# LMP9100_breakout.net
KiCad netlist of a schematic drawn in EAGLE
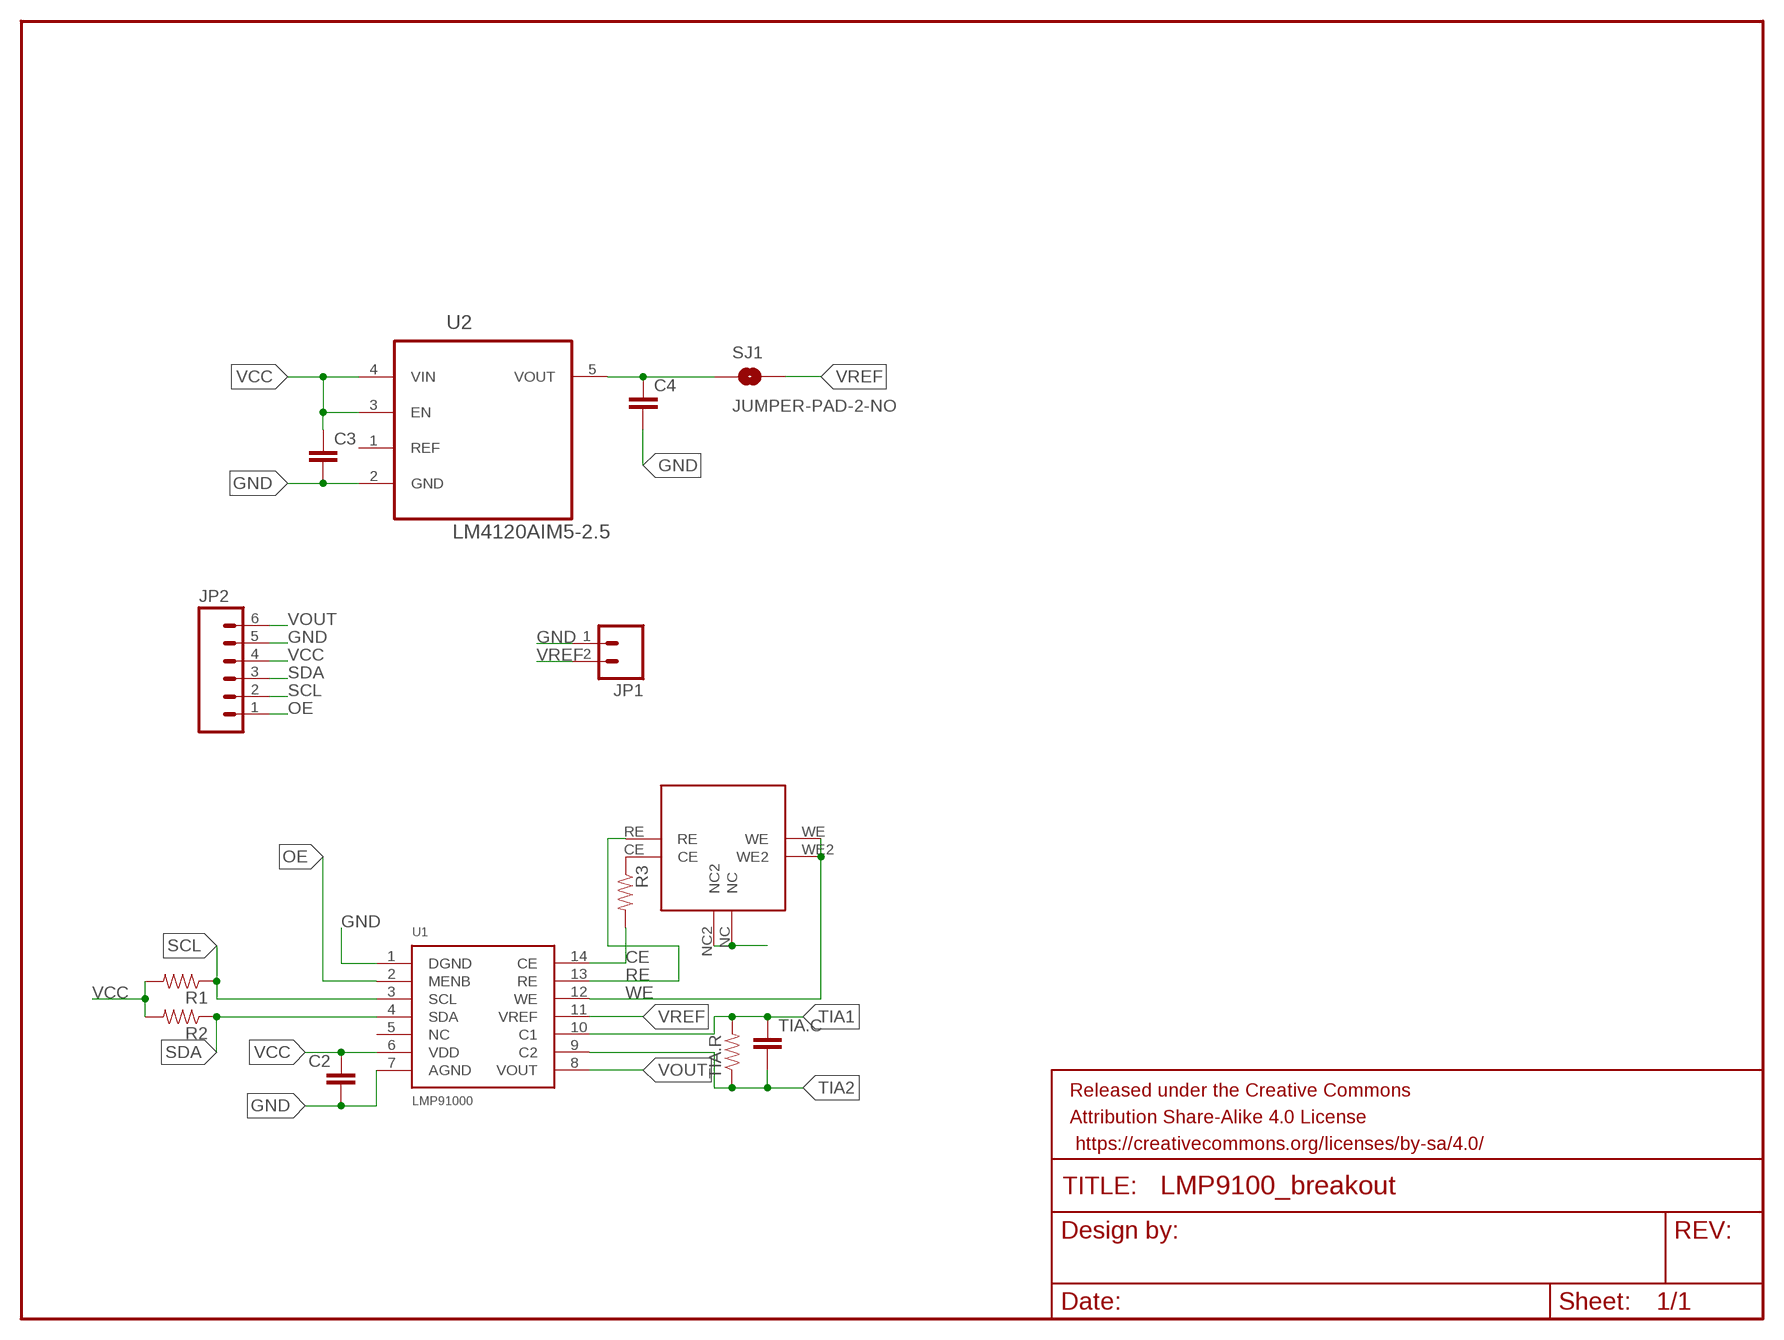
[diagram p0: schematic, sheet 1]

(export (version "E")
  (design (tool "Eeschema 10.0.6"))
  (components
    (comp (ref "C2")
      (value "CAP0603-CAP")
      (footprint "eagle-import:0603-CAP")
      (libsource (lib "eagle-import") (part "CAP0603-CAP"))
    )
    (comp (ref "C3")
      (value "CAP0603-CAP")
      (footprint "eagle-import:0603-CAP")
      (libsource (lib "eagle-import") (part "CAP0603-CAP"))
    )
    (comp (ref "C4")
      (value "CAP0603-CAP")
      (footprint "eagle-import:0603-CAP")
      (libsource (lib "eagle-import") (part "CAP0603-CAP"))
    )
    (comp (ref "FRAME1")
      (value "FRAME-LETTER")
      (footprint "eagle-import:CREATIVE_COMMONS")
      (libsource (lib "eagle-import") (part "FRAME-LETTER"))
    )
    (comp (ref "JP1")
      (value "M02PTH")
      (footprint "eagle-import:1X02")
      (libsource (lib "eagle-import") (part "M02PTH"))
    )
    (comp (ref "JP2")
      (value "M06SILK_FEMALE_PTH")
      (footprint "eagle-import:1X06")
      (libsource (lib "eagle-import") (part "M06SILK_FEMALE_PTH"))
    )
    (comp (ref "R1")
      (value "RESISTOR0603-RES")
      (footprint "eagle-import:0603-RES")
      (libsource (lib "eagle-import") (part "RESISTOR0603-RES"))
    )
    (comp (ref "R2")
      (value "RESISTOR0603-RES")
      (footprint "eagle-import:0603-RES")
      (libsource (lib "eagle-import") (part "RESISTOR0603-RES"))
    )
    (comp (ref "R3")
      (value "RESISTOR0603-RES")
      (footprint "eagle-import:0603-RES")
      (libsource (lib "eagle-import") (part "RESISTOR0603-RES"))
    )
    (comp (ref "SJ1")
      (value "JUMPER-PAD-2-NO")
      (footprint "eagle-import:PAD-JUMPER-2-NO_NO_SILK")
      (libsource (lib "eagle-import") (part "JUMPER-PAD-2-NO"))
    )
    (comp (ref "TIA.C")
      (value "CAP0603-CAP")
      (footprint "eagle-import:0603-CAP")
      (libsource (lib "eagle-import") (part "CAP0603-CAP"))
    )
    (comp (ref "TIA.R")
      (value "RESISTOR0603-RES")
      (footprint "eagle-import:0603-RES")
      (libsource (lib "eagle-import") (part "RESISTOR0603-RES"))
    )
    (comp (ref "U$1")
      (value "SPEC-SENSOR")
      (footprint "eagle-import:SPEC-SENSOR")
      (libsource (lib "eagle-import") (part "SPEC-SENSOR"))
    )
    (comp (ref "U1")
      (value "LMP91000")
      (footprint "eagle-import:LMP91000")
      (libsource (lib "eagle-import") (part "LMP91000"))
    )
    (comp (ref "U2")
      (value "LM4120AIM5-2.5")
      (footprint "eagle-import:SOT95P284X122-5N")
      (fields (field (name "MF") "Texas Instruments") (field (name "MP") "LM4120AIM5-2.5/NOPB"))
      (libsource (lib "eagle-import") (part "LM4120AIM5-2.5"))
    )
  )
  (nets
    (net (code "1") (name "/CE") (class "Default")
      (node (ref "R3") (pin "2") (pinfunction "2_2") (pintype "passive"))
      (node (ref "U1") (pin "14") (pinfunction "CE_14") (pintype "bidirectional"))
    )
    (net (code "2") (name "/RE") (class "Default")
      (node (ref "U$1") (pin "RE") (pinfunction "RE_RE") (pintype "bidirectional"))
      (node (ref "U1") (pin "13") (pinfunction "RE_13") (pintype "bidirectional"))
    )
    (net (code "3") (name "/WE") (class "Default")
      (node (ref "U$1") (pin "WE") (pinfunction "WE_WE") (pintype "bidirectional"))
      (node (ref "U$1") (pin "WE2") (pinfunction "WE2_WE2") (pintype "bidirectional"))
      (node (ref "U1") (pin "12") (pinfunction "WE_12") (pintype "bidirectional"))
    )
    (net (code "4") (name "GND") (class "Default")
      (node (ref "C2") (pin "2") (pinfunction "2_2") (pintype "passive"))
      (node (ref "C3") (pin "2") (pinfunction "2_2") (pintype "passive"))
      (node (ref "C4") (pin "2") (pinfunction "2_2") (pintype "passive"))
      (node (ref "JP1") (pin "1") (pinfunction "1_1") (pintype "passive"))
      (node (ref "JP2") (pin "5") (pinfunction "5_5") (pintype "passive"))
      (node (ref "U$1") (pin "NC") (pinfunction "NC_NC") (pintype "bidirectional"))
      (node (ref "U$1") (pin "NC2") (pinfunction "NC2_NC2") (pintype "bidirectional"))
      (node (ref "U1") (pin "1") (pinfunction "DGND_1") (pintype "bidirectional"))
      (node (ref "U1") (pin "7") (pinfunction "AGND_7") (pintype "bidirectional"))
      (node (ref "U2") (pin "2") (pinfunction "GND_2") (pintype "passive"))
    )
    (net (code "5") (name "Net-(R3-Pad1)") (class "Default")
      (node (ref "R3") (pin "1") (pinfunction "1_1") (pintype "passive"))
      (node (ref "U$1") (pin "CE") (pinfunction "CE_CE") (pintype "bidirectional"))
    )
    (net (code "6") (name "Net-(U2-VOUT)") (class "Default")
      (node (ref "C4") (pin "1") (pinfunction "1_1") (pintype "passive"))
      (node (ref "SJ1") (pin "1") (pinfunction "1_1") (pintype "passive"))
      (node (ref "U2") (pin "5") (pinfunction "VOUT_5") (pintype "output"))
    )
    (net (code "7") (name "OE") (class "Default")
      (node (ref "JP2") (pin "1") (pinfunction "1_1") (pintype "passive"))
      (node (ref "U1") (pin "2") (pinfunction "MENB_2") (pintype "bidirectional"))
    )
    (net (code "8") (name "SCL") (class "Default")
      (node (ref "JP2") (pin "2") (pinfunction "2_2") (pintype "passive"))
      (node (ref "R1") (pin "1") (pinfunction "1_1") (pintype "passive"))
      (node (ref "U1") (pin "3") (pinfunction "SCL_3") (pintype "bidirectional"))
    )
    (net (code "9") (name "SDA") (class "Default")
      (node (ref "JP2") (pin "3") (pinfunction "3_3") (pintype "passive"))
      (node (ref "R2") (pin "1") (pinfunction "1_1") (pintype "passive"))
      (node (ref "U1") (pin "4") (pinfunction "SDA_4") (pintype "bidirectional"))
    )
    (net (code "10") (name "TIA1") (class "Default")
      (node (ref "TIA.C") (pin "1") (pinfunction "1_1") (pintype "passive"))
      (node (ref "TIA.R") (pin "2") (pinfunction "2_2") (pintype "passive"))
      (node (ref "U1") (pin "10") (pinfunction "C1_10") (pintype "bidirectional"))
    )
    (net (code "11") (name "TIA2") (class "Default")
      (node (ref "TIA.C") (pin "2") (pinfunction "2_2") (pintype "passive"))
      (node (ref "TIA.R") (pin "1") (pinfunction "1_1") (pintype "passive"))
      (node (ref "U1") (pin "9") (pinfunction "C2_9") (pintype "bidirectional"))
    )
    (net (code "12") (name "VCC") (class "Default")
      (node (ref "C2") (pin "1") (pinfunction "1_1") (pintype "passive"))
      (node (ref "C3") (pin "1") (pinfunction "1_1") (pintype "passive"))
      (node (ref "JP2") (pin "4") (pinfunction "4_4") (pintype "passive"))
      (node (ref "R1") (pin "2") (pinfunction "2_2") (pintype "passive"))
      (node (ref "R2") (pin "2") (pinfunction "2_2") (pintype "passive"))
      (node (ref "U1") (pin "6") (pinfunction "VDD_6") (pintype "bidirectional"))
      (node (ref "U2") (pin "3") (pinfunction "EN_3") (pintype "input"))
      (node (ref "U2") (pin "4") (pinfunction "VIN_4") (pintype "input"))
    )
    (net (code "13") (name "VOUT") (class "Default")
      (node (ref "JP2") (pin "6") (pinfunction "6_6") (pintype "passive"))
      (node (ref "U1") (pin "8") (pinfunction "VOUT_8") (pintype "bidirectional"))
    )
    (net (code "14") (name "VREF") (class "Default")
      (node (ref "JP1") (pin "2") (pinfunction "2_2") (pintype "passive"))
      (node (ref "SJ1") (pin "2") (pinfunction "2_2") (pintype "passive"))
      (node (ref "U1") (pin "11") (pinfunction "VREF_11") (pintype "bidirectional"))
    )
    (net (code "15") (name "unconnected-(U1-NC-Pad5)") (class "Default")
      (node (ref "U1") (pin "5") (pinfunction "NC_5") (pintype "bidirectional"))
    )
    (net (code "16") (name "unconnected-(U2-REF-Pad1)") (class "Default")
      (node (ref "U2") (pin "1") (pinfunction "REF_1") (pintype "passive"))
    )
  )
)
